# Ethernet.net
KiCad netlist of a schematic drawn in Altium Designer
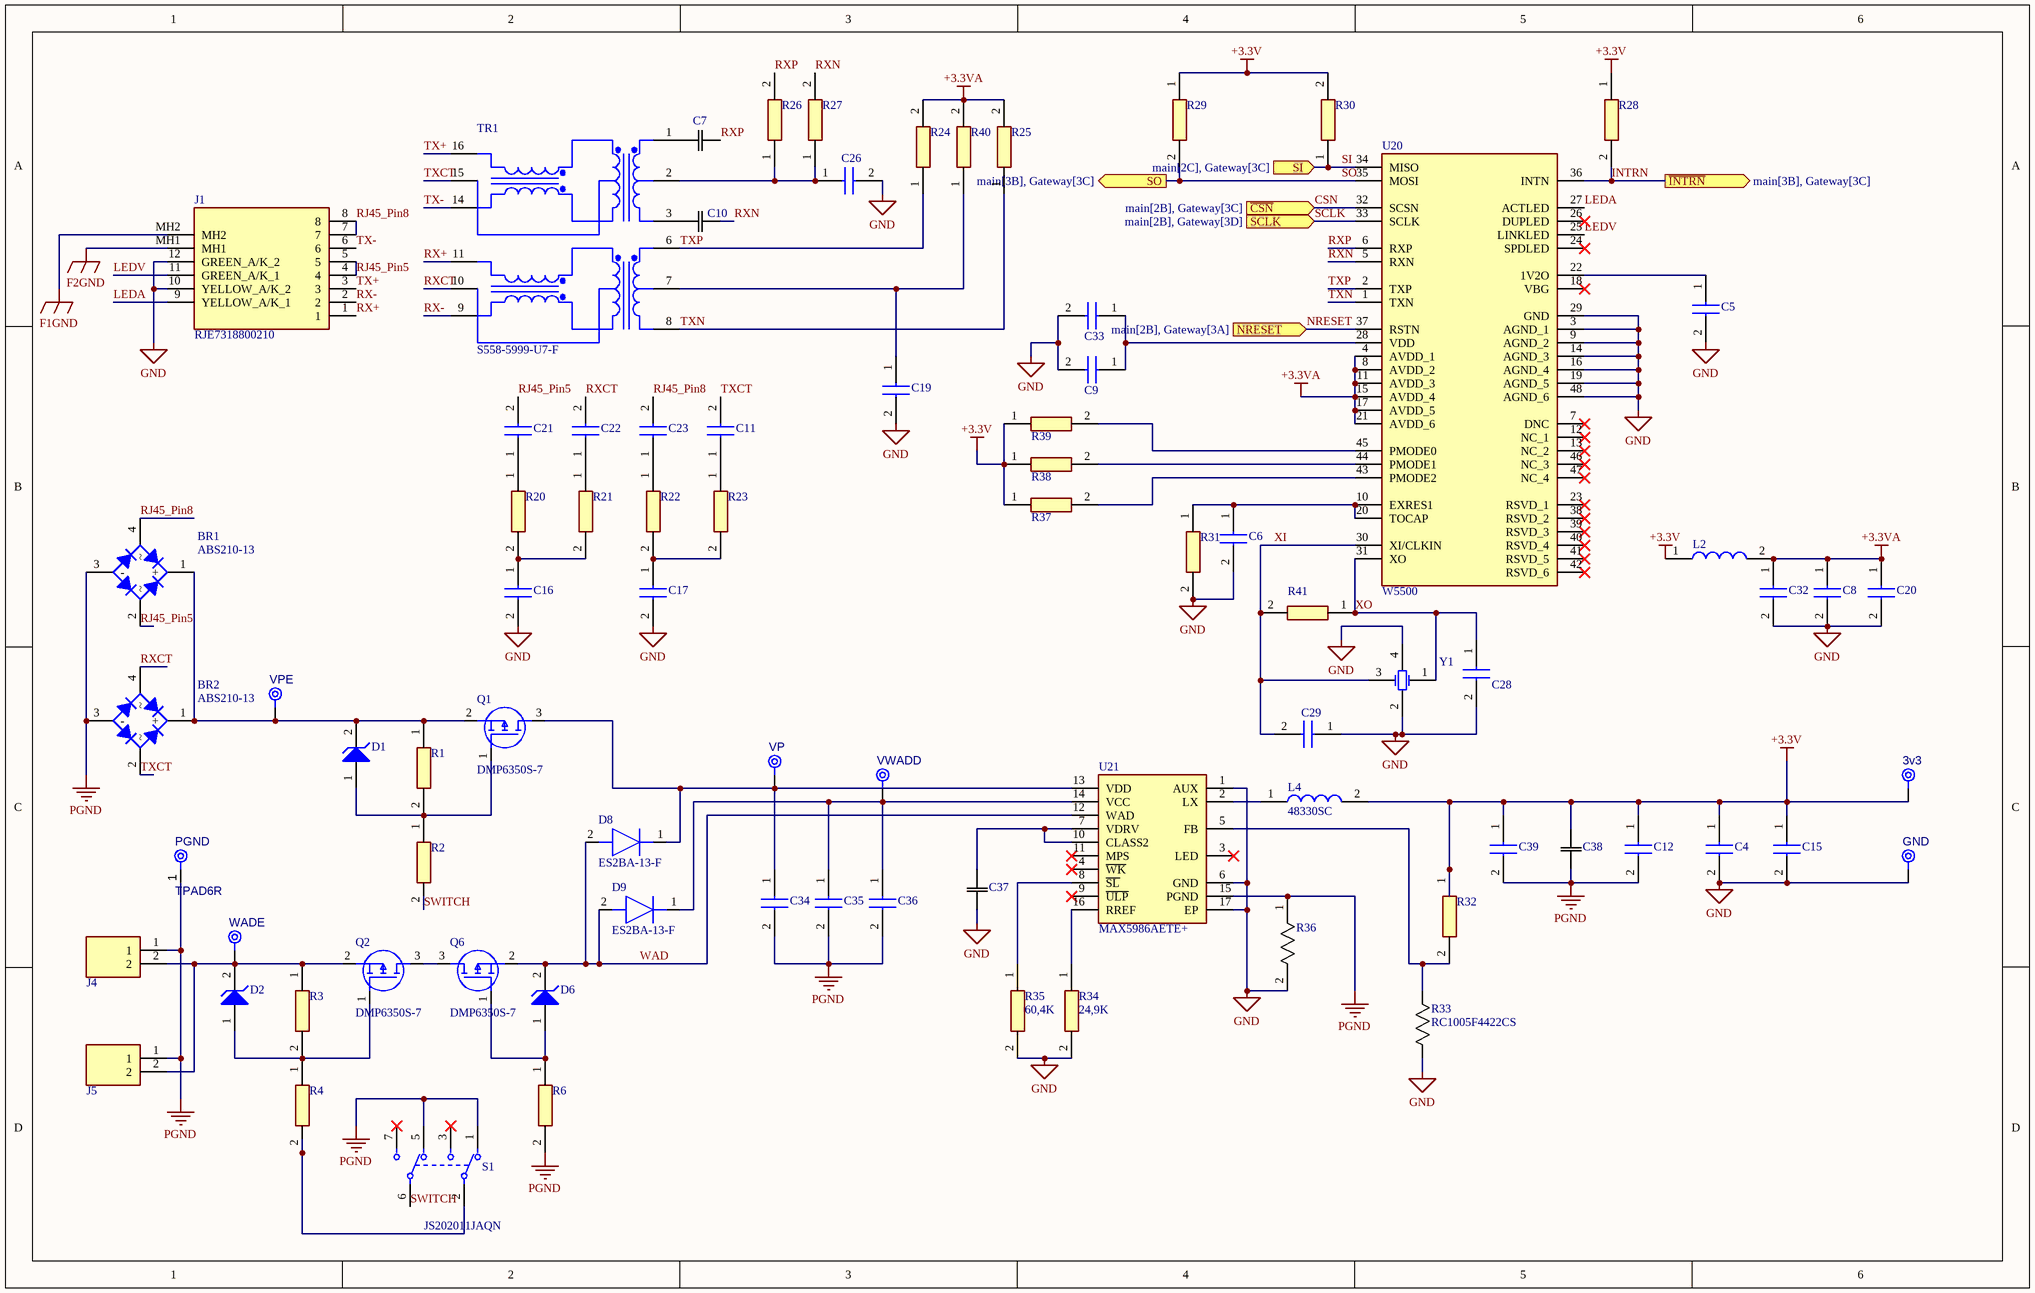
[diagram p0: Ethernet.SchDoc]

(export (version "E")
  (design (tool "Eeschema 10.0.6"))
  (components
    (comp (ref "3v3")
      (value "TPAD6R")
      (footprint "TP06R")
      (description "0.6mm round")
      (libsource (lib "marina santos") (part "CMP-001-0001-4"))
    )
    (comp (ref "BR1")
      (value "ABS210-13")
      (footprint "SamacSys:ABS21013")
      (description "Bridge Rectifier")
      (fields (field (name "MOUSER PART NUMBER") "621-ABS210-13"))
      (libsource (lib "SamacSys") (part "ABS210-13"))
    )
    (comp (ref "BR2")
      (value "ABS210-13")
      (footprint "SamacSys:ABS21013")
      (description "Bridge Rectifier")
      (fields (field (name "MOUSER PART NUMBER") "621-ABS210-13"))
      (libsource (lib "SamacSys") (part "ABS210-13"))
    )
    (comp (ref "C4")
      (value "C1005X7R1C104KT")
      (footprint "SamacSys:CAPC1005X55N")
      (description "Capacitor")
      (libsource (lib "*") (part "C1005X7R1C104KT"))
    )
    (comp (ref "C5")
      (value "CL05B103KO5NNNC")
      (footprint "SamacSys:CAPC1005X55N")
      (description "Capacitor 10n")
      (libsource (lib "*") (part "CL05B103KO5NNNC"))
    )
    (comp (ref "C6")
      (value "JMK105BC6475MV-F")
      (footprint "SamacSys:CAPC1006X65N")
      (description "Capacitor 4,7u")
      (fields (field (name "MOUSER PART NUMBER") "963-JMK105BC6475MV-F"))
      (libsource (lib "*") (part "JMK105BC6475MV-F"))
    )
    (comp (ref "C7")
      (value "CL05X105KP5NNNC")
      (footprint "CAP_CL05_SAM")
      (description "No Description Available")
      (libsource (lib "CL05X105KP5NNNC") (part "CL05X105KP5NNNC"))
    )
    (comp (ref "C8")
      (value "C1005X7R1C104KT")
      (footprint "SamacSys:CAPC1005X55N")
      (description "Capacitor 100n")
      (libsource (lib "*") (part "C1005X7R1C104KT"))
    )
    (comp (ref "C9")
      (value "C1005X7R1C104KT")
      (footprint "SamacSys:CAPC1005X55N")
      (description "Capacitor 100n")
      (libsource (lib "*") (part "C1005X7R1C104KT"))
    )
    (comp (ref "C10")
      (value "CL05X105KP5NNNC")
      (footprint "CAP_CL05_SAM")
      (description "No Description Available")
      (libsource (lib "CL05X105KP5NNNC") (part "CL05X105KP5NNNC"))
    )
    (comp (ref "C11")
      (value "C1608JB2A223M080AA")
      (footprint "SamacSys:C1608_Commercial")
      (description "Capacitor")
      (fields (field (name "MOUSER PART NUMBER") "810-C1608JB2A223M08A"))
      (libsource (lib "*") (part "C1608JB2A223M080AA"))
    )
    (comp (ref "C12")
      (value "C1005X7R1C104KT")
      (footprint "SamacSys:CAPC1005X55N")
      (description "Capacitor")
      (libsource (lib "*") (part "C1005X7R1C104KT"))
    )
    (comp (ref "C15")
      (value "CL05A106MP8NUB8")
      (footprint "SamacSys:CAPC1005X90N")
      (description "Capacitor 10u")
      (fields (field (name "MOUSER PART NUMBER") "187-CL05A106MP8NUB8"))
      (libsource (lib "*") (part "CL05A106MP8NUB8"))
    )
    (comp (ref "C16")
      (value "CL31B102KJHNNNE")
      (footprint "SamacSys:CAPC3216X180N")
      (description "Capacitor")
      (fields (field (name "MOUSER PART NUMBER") "187-CL31B102KJHNNNE"))
      (libsource (lib "*") (part "CL31B102KJHNNNE"))
    )
    (comp (ref "C17")
      (value "CL31B102KJHNNNE")
      (footprint "SamacSys:CAPC3216X180N")
      (description "Capacitor")
      (fields (field (name "MOUSER PART NUMBER") "187-CL31B102KJHNNNE"))
      (libsource (lib "*") (part "CL31B102KJHNNNE"))
    )
    (comp (ref "C19")
      (value "GRM155R71H223KA12D")
      (footprint "SamacSys:GRM15x")
      (description "Capacitor")
      (fields (field (name "MOUSER PART NUMBER") "81-GRM155R71H223KA12"))
      (libsource (lib "*") (part "GRM155R71H223KA12D"))
    )
    (comp (ref "C20")
      (value "CL05B103KO5NNNC")
      (footprint "SamacSys:CAPC1005X55N")
      (description "Capacitor 10n")
      (libsource (lib "*") (part "CL05B103KO5NNNC"))
    )
    (comp (ref "C21")
      (value "C1608JB2A223M080AA")
      (footprint "SamacSys:C1608_Commercial")
      (description "Capacitor")
      (fields (field (name "MOUSER PART NUMBER") "810-C1608JB2A223M08A"))
      (libsource (lib "*") (part "C1608JB2A223M080AA"))
    )
    (comp (ref "C22")
      (value "C1608JB2A223M080AA")
      (footprint "SamacSys:C1608_Commercial")
      (description "Capacitor")
      (fields (field (name "MOUSER PART NUMBER") "810-C1608JB2A223M08A"))
      (libsource (lib "*") (part "C1608JB2A223M080AA"))
    )
    (comp (ref "C23")
      (value "C1608JB2A223M080AA")
      (footprint "SamacSys:C1608_Commercial")
      (description "Capacitor")
      (fields (field (name "MOUSER PART NUMBER") "810-C1608JB2A223M08A"))
      (libsource (lib "*") (part "C1608JB2A223M080AA"))
    )
    (comp (ref "C26")
      (value "C1005X5R1E104K050BC")
      (footprint "SamacSys:CAPC1005X55N")
      (description "Capacitor")
      (fields (field (name "MOUSER PART NUMBER") "810-C1005X5R1E104K"))
      (libsource (lib "*") (part "C1005X5R1E104K050BC"))
    )
    (comp (ref "C28")
      (value "C1005C0G1H150JT")
      (footprint "SamacSys:CAPC1005X55N")
      (description "Capacitor 15pF")
      (fields (field (name "MANUFACTURER_PART_NUMBER") "CC0402JRNPO9BN150"))
      (libsource (lib "*") (part "CC0402JRNPO9BN150"))
    )
    (comp (ref "C29")
      (value "C1005C0G1H150JT")
      (footprint "SamacSys:CAPC1005X55N")
      (description "Capacitor 15pF")
      (fields (field (name "MANUFACTURER_PART_NUMBER") "CC0402JRNPO9BN150"))
      (libsource (lib "*") (part "CC0402JRNPO9BN150"))
    )
    (comp (ref "C32")
      (value "JMK105BC6475MV-F")
      (footprint "SamacSys:CAPC1006X65N")
      (description "Capacitor 4,7u")
      (fields (field (name "MOUSER PART NUMBER") "963-JMK105BC6475MV-F"))
      (libsource (lib "*") (part "JMK105BC6475MV-F"))
    )
    (comp (ref "C33")
      (value "JMK105BC6475MV-F")
      (footprint "SamacSys:CAPC1006X65N")
      (description "Capacitor 4,7u")
      (fields (field (name "MOUSER PART NUMBER") "963-JMK105BC6475MV-F"))
      (libsource (lib "*") (part "JMK105BC6475MV-F"))
    )
    (comp (ref "C34")
      (value "CC0805KKX7R0BB683")
      (footprint "SamacSys:CAPC2012X145N")
      (description "Capacitor 0,068u")
      (fields (field (name "MOUSER PART NUMBER") "603-CC0805KR0BB683"))
      (libsource (lib "*") (part "CC0805KKX7R0BB683"))
    )
    (comp (ref "C35")
      (value "CL21Y105KCYVPNE")
      (footprint "SamacSys:CAPC2012X145N")
      (description "Capacitor")
      (libsource (lib "SamacSys") (part "CL21Y105KCYVPNE"))
    )
    (comp (ref "C36")
      (value "GRM32ER71J106KA12L")
      (footprint "SamacSys:CAPC3225X270N")
      (description "Capacitor 10u")
      (fields (field (name "MOUSER PART NUMBER") "81-GRM32ER71J106KA2L"))
      (libsource (lib "*") (part "GRM32ER71J106KA12L"))
    )
    (comp (ref "C37")
      (value "CL05X105KP5NNNC")
      (footprint "CAP_CL_05_SAM")
      (description "1u")
      (libsource (lib "CL05X105KP5NNNC") (part "CL05X105KP5NNNC"))
    )
    (comp (ref "C38")
      (value "CL05X105KP5NNNC")
      (footprint "CAP_CL_05_SAM")
      (description "No Description Available")
      (libsource (lib "CL05X105KP5NNNC") (part "CL05X105KP5NNNC"))
    )
    (comp (ref "C39")
      (value "GRM21BR61A476ME15L")
      (footprint "SamacSys:CAPC2012X145N")
      (description "Capacitor")
      (fields (field (name "MOUSER PART NUMBER") "81-GRM21BR61A476ME5L"))
      (libsource (lib "*") (part "GRM21BR61A476ME15L"))
    )
    (comp (ref "D1")
      (value "MMSZ5240B-7-F")
      (footprint "SamacSys:SOD3716X145N")
      (description "D2")
      (fields (field (name "MOUSER PART NUMBER") "621-MMSZ5240B-F"))
      (libsource (lib "SamacSys") (part "MMSZ5240B-7-F"))
    )
    (comp (ref "D2")
      (value "MMSZ5240B-7-F")
      (footprint "SamacSys:SOD3716X145N")
      (description "D2")
      (fields (field (name "MOUSER PART NUMBER") "621-MMSZ5240B-F"))
      (libsource (lib "SamacSys") (part "MMSZ5240B-7-F"))
    )
    (comp (ref "D6")
      (value "MMSZ5240B-7-F")
      (footprint "SamacSys:SOD3716X145N")
      (description "D2")
      (fields (field (name "MOUSER PART NUMBER") "621-MMSZ5240B-F"))
      (libsource (lib "SamacSys") (part "MMSZ5240B-7-F"))
    )
    (comp (ref "D8")
      (value "ES2BA-13-F")
      (footprint "SamacSys:DIOM5226X230N")
      (description "Diode")
      (fields (field (name "MOUSER PART NUMBER") "621-ES2BA-F"))
      (libsource (lib "*") (part "ES2BA-13-F"))
    )
    (comp (ref "D9")
      (value "ES2BA-13-F")
      (footprint "SamacSys:DIOM5226X230N")
      (description "Diode")
      (fields (field (name "MOUSER PART NUMBER") "621-ES2BA-F"))
      (libsource (lib "*") (part "ES2BA-13-F"))
    )
    (comp (ref "GND")
      (value "TPAD6R")
      (footprint "TP06R")
      (description "0.6mm round")
      (libsource (lib "marina santos") (part "CMP-001-0001-4"))
    )
    (comp (ref "J1")
      (value "RJE7318800210")
      (footprint "SamacSys:RJE7318800210")
      (description "Connector")
      (fields (field (name "MOUSER PART NUMBER") "523-RJE7318800210"))
      (libsource (lib "SamacSys") (part "RJE7318800210"))
    )
    (comp (ref "J4")
      (value "OQ0232510000G")
      (footprint "SamacSys:OQ0232510000G")
      (description "Connector")
      (fields (field (name "MOUSER PART NUMBER") "649-220110-D021A01LF"))
      (libsource (lib "*") (part "OQ0232510000G"))
    )
    (comp (ref "J5")
      (value "OQ0232510000G")
      (footprint "SamacSys:OQ0232510000G")
      (description "Connector")
      (fields (field (name "MOUSER PART NUMBER") "649-220110-D021A01LF"))
      (libsource (lib "*") (part "OQ0232510000G"))
    )
    (comp (ref "L2")
      (value "FBMH1608HM101-T")
      (footprint "SamacSys:INDC1608X90N")
      (description "Ferrite Bead")
      (fields (field (name "MOUSER PART NUMBER") "963-FBMH1608HM101-T"))
      (libsource (lib "SamacSys") (part "FBMH1608HM101-T"))
    )
    (comp (ref "L4")
      (value "48330SC")
      (footprint "SamacSys:48101SC")
      (description "Inductor")
      (fields
        (field (name "MANUFACTURER_PART_NUMBER") "48101SC")
        (field (name "MOUSER PART NUMBER") "580-48101SC")
      )
      (libsource (lib "SamacSys") (part "48101SC"))
    )
    (comp (ref "PGND")
      (value "TPAD6R")
      (footprint "TP06R")
      (description "0.6mm round")
      (libsource (lib "") (part "CMP-001-0001-4_1"))
    )
    (comp (ref "Q1")
      (value "DMP6350S-7")
      (footprint "SamacSys:SOT96P240X110-3N")
      (description "MOSFET (P-Channel)")
      (fields (field (name "MOUSER PART NUMBER") "621-DMP6350S-7"))
      (libsource (lib "*") (part "DMP6350S-7"))
    )
    (comp (ref "Q2")
      (value "DMP6350S-7")
      (footprint "SamacSys:SOT96P240X110-3N")
      (description "MOSFET (P-Channel)")
      (fields (field (name "MOUSER PART NUMBER") "621-DMP6350S-7"))
      (libsource (lib "*") (part "DMP6350S-7"))
    )
    (comp (ref "Q6")
      (value "DMP6350S-7")
      (footprint "SamacSys:SOT96P240X110-3N")
      (description "MOSFET (P-Channel)")
      (fields (field (name "MOUSER PART NUMBER") "621-DMP6350S-7"))
      (libsource (lib "*") (part "DMP6350S-7"))
    )
    (comp (ref "R1")
      (value "R0402_1%_100_K__RC0402FR-07100KL_")
      (footprint "SamacSys:RESC1005X40N")
      (description "Resistor 100k")
      (fields (field (name "MANUFACTURER_PART_NUMBER") "R0402 1% 100 K (RC0402FR-07100KL)"))
      (libsource (lib "*") (part "R0402_1%_100_K__RC0402FR-07100KL_"))
    )
    (comp (ref "R2")
      (value "R0402_1%_100_K__RC0402FR-07100KL_")
      (footprint "SamacSys:RESC1005X40N")
      (description "Resistor 100k")
      (fields (field (name "MANUFACTURER_PART_NUMBER") "R0402 1% 100 K (RC0402FR-07100KL)"))
      (libsource (lib "*") (part "R0402_1%_100_K__RC0402FR-07100KL_"))
    )
    (comp (ref "R3")
      (value "R0402_1%_100_K__RC0402FR-07100KL_")
      (footprint "SamacSys:RESC1005X40N")
      (description "Resistor 100k")
      (fields (field (name "MANUFACTURER_PART_NUMBER") "R0402 1% 100 K (RC0402FR-07100KL)"))
      (libsource (lib "*") (part "R0402_1%_100_K__RC0402FR-07100KL_"))
    )
    (comp (ref "R4")
      (value "R0402_1%_100_K__RC0402FR-07100KL_")
      (footprint "SamacSys:RESC1005X40N")
      (description "Resistor 100k")
      (fields (field (name "MANUFACTURER_PART_NUMBER") "R0402 1% 100 K (RC0402FR-07100KL)"))
      (libsource (lib "*") (part "R0402_1%_100_K__RC0402FR-07100KL_"))
    )
    (comp (ref "R6")
      (value "R0402_1%_100_K__RC0402FR-07100KL_")
      (footprint "SamacSys:RESC1005X40N")
      (description "Resistor 100k")
      (fields (field (name "MANUFACTURER_PART_NUMBER") "R0402 1% 100 K (RC0402FR-07100KL)"))
      (libsource (lib "*") (part "R0402_1%_100_K__RC0402FR-07100KL_"))
    )
    (comp (ref "R20")
      (value "RC0603FR-0775RL")
      (footprint "SamacSys:RESC1608X55N")
      (description "Resistor")
      (fields (field (name "MOUSER PART NUMBER") "603-RC0603FR-0775RL"))
      (libsource (lib "*") (part "RC0603FR-0775RL"))
    )
    (comp (ref "R21")
      (value "RC0603FR-0775RL")
      (footprint "SamacSys:RESC1608X55N")
      (description "Resistor")
      (fields (field (name "MOUSER PART NUMBER") "603-RC0603FR-0775RL"))
      (libsource (lib "*") (part "RC0603FR-0775RL"))
    )
    (comp (ref "R22")
      (value "RC0603FR-0775RL")
      (footprint "SamacSys:RESC1608X55N")
      (description "Resistor")
      (fields (field (name "MOUSER PART NUMBER") "603-RC0603FR-0775RL"))
      (libsource (lib "*") (part "RC0603FR-0775RL"))
    )
    (comp (ref "R23")
      (value "RC0603FR-0775RL")
      (footprint "SamacSys:RESC1608X55N")
      (description "Resistor")
      (fields (field (name "MOUSER PART NUMBER") "603-RC0603FR-0775RL"))
      (libsource (lib "*") (part "RC0603FR-0775RL"))
    )
    (comp (ref "R24")
      (value "RC0402FR-0749R9L")
      (footprint "SamacSys:RESC1005X40N")
      (description "Resistor 49,9 ohms")
      (fields (field (name "MOUSER PART NUMBER") "603-RC0402FR-0749R9L"))
      (libsource (lib "*") (part "RC0402FR-0749R9L"))
    )
    (comp (ref "R25")
      (value "RC0402FR-0749R9L")
      (footprint "SamacSys:RESC1005X40N")
      (description "Resistor 49,9 ohms")
      (fields (field (name "MOUSER PART NUMBER") "603-RC0402FR-0749R9L"))
      (libsource (lib "*") (part "RC0402FR-0749R9L"))
    )
    (comp (ref "R26")
      (value "RC0402FR-0782RL")
      (footprint "SamacSys:RESC1005X40N")
      (description "Resistor")
      (fields (field (name "MOUSER PART NUMBER") "603-RC0402FR-0782RL"))
      (libsource (lib "*") (part "RC0402FR-0782RL"))
    )
    (comp (ref "R27")
      (value "RC0402FR-0782RL")
      (footprint "SamacSys:RESC1005X40N")
      (description "Resistor")
      (fields (field (name "MOUSER PART NUMBER") "603-RC0402FR-0782RL"))
      (libsource (lib "*") (part "RC0402FR-0782RL"))
    )
    (comp (ref "R28")
      (value "RC0402FR-074K7L")
      (footprint "SamacSys:RESC1005X40N")
      (description "Resistor 4,7K")
      (fields (field (name "MOUSER PART NUMBER") "603-RC0402FR-074K7L"))
      (libsource (lib "*") (part "RC0402FR-074K7L"))
    )
    (comp (ref "R29")
      (value "RC0402FR-074K7L")
      (footprint "SamacSys:RESC1005X40N")
      (description "Resistor 4,7K")
      (fields (field (name "MOUSER PART NUMBER") "603-RC0402FR-074K7L"))
      (libsource (lib "*") (part "RC0402FR-074K7L"))
    )
    (comp (ref "R30")
      (value "RC0402FR-074K7L")
      (footprint "SamacSys:RESC1005X40N")
      (description "Resistor 4,7 K")
      (fields (field (name "MOUSER PART NUMBER") "603-RC0402FR-074K7L"))
      (libsource (lib "") (part "RC0402FR-074K7L_1"))
    )
    (comp (ref "R31")
      (value "RC0402FR-0712K4L")
      (footprint "SamacSys:RESC1005X40N")
      (description "Resistor 12,4K")
      (fields (field (name "MOUSER PART NUMBER") "603-RC0402FR-0712K4L"))
      (libsource (lib "*") (part "RC0402FR-0712K4L"))
    )
    (comp (ref "R32")
      (value "RC0402FR-0775KL")
      (footprint "SamacSys:RESC1005X40N")
      (description "Resistor")
      (fields (field (name "MOUSER PART NUMBER") "603-RC0402FR-0775KL"))
      (libsource (lib "*") (part "RC0402FR-0775KL"))
    )
    (comp (ref "R33")
      (value "RC1005F4422CS")
      (footprint "RES_1005_SAM-M")
      (description "No Description Available")
      (libsource (lib "RC1005F4422CS") (part "RC1005F4422CS"))
    )
    (comp (ref "R34")
      (value "24,9K")
      (footprint "SamacSys:RESC1005X40N")
      (description "Resistor")
      (fields
        (field (name "MANUFACTURER_PART_NUMBER") "RC0402FR-0724K9L")
        (field (name "MOUSER PART NUMBER") "603-RC0402FR-0724K9L")
      )
      (libsource (lib "*") (part "RC0402FR-0724K9L"))
    )
    (comp (ref "R35")
      (value "60,4K")
      (footprint "SamacSys:RESC1005X40N")
      (description "Resistor 60,4K")
      (fields
        (field (name "MANUFACTURER_PART_NUMBER") "RC0402FR-0760K4L")
        (field (name "MOUSER PART NUMBER") "603-RC0402FR-0760K4L")
      )
      (libsource (lib "*") (part "RC0402FR-0760K4L"))
    )
    (comp (ref "R36")
      (value "RC0805JR-070RL")
      (footprint "SamacSys:CAPC2012X60N")
      (description "Capacitor 0 ohms")
      (fields (field (name "MOUSER PART NUMBER") "603-RC0805JR-070RL"))
      (libsource (lib "SamacSys") (part "RC0805JR-070RL"))
    )
    (comp (ref "R37")
      (value "RC0402FR-0710KL")
      (footprint "SamacSys:RESC1005X40N")
      (description "Resistor 10K")
      (fields (field (name "MOUSER PART NUMBER") "603-RC0402FR-0710KL"))
      (libsource (lib "*") (part "RC0402FR-0710KL"))
    )
    (comp (ref "R38")
      (value "RC0402FR-0710KL")
      (footprint "SamacSys:RESC1005X40N")
      (description "Resistor 10K")
      (fields (field (name "MOUSER PART NUMBER") "603-RC0402FR-0710KL"))
      (libsource (lib "*") (part "RC0402FR-0710KL"))
    )
    (comp (ref "R39")
      (value "RC0402FR-0710KL")
      (footprint "SamacSys:RESC1005X40N")
      (description "Resistor 10K")
      (fields (field (name "MOUSER PART NUMBER") "603-RC0402FR-0710KL"))
      (libsource (lib "*") (part "RC0402FR-0710KL"))
    )
    (comp (ref "R40")
      (value "RC0402FR-0710RL")
      (footprint "SamacSys:RESC1005X40N")
      (description "Resistor 10 ohms")
      (fields (field (name "MOUSER PART NUMBER") "603-RC0402FR-0710RL"))
      (libsource (lib "*") (part "RC0402FR-0710RL"))
    )
    (comp (ref "R41")
      (value "RC0402FR-071ML")
      (footprint "SamacSys:RESC1005X40N")
      (description "Resistor 1M")
      (fields (field (name "MOUSER PART NUMBER") "603-RC0402FR-071ML"))
      (libsource (lib "*") (part "RC0402FR-071ML"))
    )
    (comp (ref "S1")
      (value "JS202011JAQN")
      (footprint "C&K_0_MFG")
      (libsource (lib "Switch_C&K_JS202011JAQN_eec") (part "JS202011JAQN"))
    )
    (comp (ref "TR1")
      (value "S558-5999-U7-F")
      (footprint "SamacSys:SOIC127P920X571-16N")
      (description "Integrated Circuit")
      (fields (field (name "MOUSER PART NUMBER") "530-S558-5999-U7-F"))
      (libsource (lib "SamacSys") (part "S558-5999-U7-F"))
    )
    (comp (ref "U20")
      (value "W5500")
      (footprint "SamacSys:QFP50P900X900X160-48N")
      (description "Integrated Circuit")
      (fields (field (name "MOUSER PART NUMBER") "950-W5500"))
      (libsource (lib "SamacSys") (part "W5500"))
    )
    (comp (ref "U21")
      (value "MAX5986AETE+")
      (footprint "SamacSys:QFN80P500X500X80-17N")
      (description "Integrated Circuit")
      (fields (field (name "MOUSER PART NUMBER") "700-MAX5986AETE+"))
      (libsource (lib "SamacSys") (part "MAX5986AETE+"))
    )
    (comp (ref "VP")
      (value "TPAD6R")
      (footprint "TP06R")
      (description "0.6mm round")
      (libsource (lib "marina santos") (part "CMP-001-0001-4"))
    )
    (comp (ref "VPE")
      (value "TPAD6R")
      (footprint "TP06R")
      (description "0.6mm round")
      (libsource (lib "marina santos") (part "CMP-001-0001-4"))
    )
    (comp (ref "VWADD")
      (value "TPAD6R")
      (footprint "TP06R")
      (description "0.6mm round")
      (libsource (lib "marina santos") (part "CMP-001-0001-4"))
    )
    (comp (ref "WADE")
      (value "TPAD6R")
      (footprint "TP06R")
      (description "0.6mm round")
      (libsource (lib "marina santos") (part "CMP-001-0001-4"))
    )
    (comp (ref "Y1")
      (value "RH100-25.000-12-F-1010-TR")
      (footprint "SamacSys:RH1002500012F1010TR")
      (description "Crystal or Oscillator")
      (libsource (lib "SamacSys") (part "RH100-25.000-12-F-1010-TR"))
    )
  )
  (nets
    (net (code "1") (name "+3.3V") (class "Default")
      (node (ref "3v3") (pin "1") (pinfunction "TP_1") (pintype "passive"))
      (node (ref "C12") (pin "1") (pinfunction "1_1") (pintype "passive"))
      (node (ref "C15") (pin "1") (pinfunction "1_1") (pintype "passive"))
      (node (ref "C38") (pin "2") (pinfunction "2_2") (pintype "passive"))
      (node (ref "C39") (pin "1") (pinfunction "1_1") (pintype "passive"))
      (node (ref "C4") (pin "1") (pinfunction "1_1") (pintype "passive"))
      (node (ref "L2") (pin "1") (pinfunction "1_1") (pintype "passive"))
      (node (ref "L4") (pin "2") (pinfunction "2_2") (pintype "passive"))
      (node (ref "R28") (pin "1") (pinfunction "1_1") (pintype "passive"))
      (node (ref "R29") (pin "1") (pinfunction "1_1") (pintype "passive"))
      (node (ref "R30") (pin "2") (pinfunction "2_2") (pintype "passive"))
      (node (ref "R32") (pin "1") (pinfunction "1_1") (pintype "passive"))
      (node (ref "R37") (pin "1") (pinfunction "1_1") (pintype "passive"))
      (node (ref "R38") (pin "1") (pinfunction "1_1") (pintype "passive"))
      (node (ref "R39") (pin "1") (pinfunction "1_1") (pintype "passive"))
    )
    (net (code "2") (name "+3.3VA") (class "Default")
      (node (ref "C20") (pin "1") (pinfunction "1_1") (pintype "passive"))
      (node (ref "C32") (pin "1") (pinfunction "1_1") (pintype "passive"))
      (node (ref "C8") (pin "1") (pinfunction "1_1") (pintype "passive"))
      (node (ref "L2") (pin "2") (pinfunction "2_2") (pintype "passive"))
      (node (ref "R24") (pin "2") (pinfunction "2_2") (pintype "passive"))
      (node (ref "R25") (pin "2") (pinfunction "2_2") (pintype "passive"))
      (node (ref "R40") (pin "2") (pinfunction "2_2") (pintype "passive"))
      (node (ref "U20") (pin "11") (pinfunction "AVDD_3_11") (pintype "passive"))
      (node (ref "U20") (pin "15") (pinfunction "AVDD_4_15") (pintype "passive"))
      (node (ref "U20") (pin "17") (pinfunction "AVDD_5_17") (pintype "passive"))
      (node (ref "U20") (pin "21") (pinfunction "AVDD_6_21") (pintype "passive"))
      (node (ref "U20") (pin "4") (pinfunction "AVDD_1_4") (pintype "passive"))
      (node (ref "U20") (pin "8") (pinfunction "AVDD_2_8") (pintype "passive"))
    )
    (net (code "3") (name "/CSN") (class "Default")
      (node (ref "U20") (pin "32") (pinfunction "SCSN_32") (pintype "passive"))
    )
    (net (code "4") (name "/INTRN") (class "Default")
      (node (ref "R28") (pin "2") (pinfunction "2_2") (pintype "passive"))
      (node (ref "U20") (pin "36") (pinfunction "INTN_36") (pintype "passive"))
    )
    (net (code "5") (name "/LEDA") (class "Default")
      (node (ref "J1") (pin "9") (pinfunction "YELLOW_A/K_1_9") (pintype "passive"))
      (node (ref "U20") (pin "27") (pinfunction "ACTLED_27") (pintype "passive"))
    )
    (net (code "6") (name "/LEDV") (class "Default")
      (node (ref "J1") (pin "11") (pinfunction "GREEN_A/K_1_11") (pintype "passive"))
      (node (ref "U20") (pin "25") (pinfunction "LINKLED_25") (pintype "passive"))
    )
    (net (code "7") (name "/NRESET") (class "Default")
      (node (ref "U20") (pin "37") (pinfunction "RSTN_37") (pintype "passive"))
    )
    (net (code "8") (name "/RJ45_Pin5") (class "Default")
      (node (ref "BR1") (pin "2") (pinfunction "~_2") (pintype "passive"))
      (node (ref "C21") (pin "2") (pinfunction "2_2") (pintype "passive"))
      (node (ref "J1") (pin "4") (pinfunction "4_4") (pintype "passive"))
      (node (ref "J1") (pin "5") (pinfunction "5_5") (pintype "passive"))
    )
    (net (code "9") (name "/RJ45_Pin8") (class "Default")
      (node (ref "BR1") (pin "4") (pinfunction "~_4") (pintype "passive"))
      (node (ref "C23") (pin "2") (pinfunction "2_2") (pintype "passive"))
      (node (ref "J1") (pin "7") (pinfunction "7_7") (pintype "passive"))
      (node (ref "J1") (pin "8") (pinfunction "8_8") (pintype "passive"))
    )
    (net (code "10") (name "/RX+") (class "Default")
      (node (ref "J1") (pin "1") (pinfunction "1_1") (pintype "passive"))
      (node (ref "TR1") (pin "11") (pinfunction "RX+_11") (pintype "passive"))
    )
    (net (code "11") (name "/RX-") (class "Default")
      (node (ref "J1") (pin "2") (pinfunction "2_2") (pintype "passive"))
      (node (ref "TR1") (pin "9") (pinfunction "RX-_9") (pintype "passive"))
    )
    (net (code "12") (name "/RXCT") (class "Default")
      (node (ref "BR2") (pin "4") (pinfunction "~_4") (pintype "passive"))
      (node (ref "C22") (pin "2") (pinfunction "2_2") (pintype "passive"))
      (node (ref "TR1") (pin "10") (pinfunction "RXCT_10") (pintype "passive"))
    )
    (net (code "13") (name "/RXN") (class "Default")
      (node (ref "C10") (pin "2") (pinfunction "2_2") (pintype "passive"))
      (node (ref "R27") (pin "2") (pinfunction "2_2") (pintype "passive"))
      (node (ref "U20") (pin "5") (pinfunction "RXN_5") (pintype "passive"))
    )
    (net (code "14") (name "/RXP") (class "Default")
      (node (ref "C7") (pin "2") (pinfunction "2_2") (pintype "passive"))
      (node (ref "R26") (pin "2") (pinfunction "2_2") (pintype "passive"))
      (node (ref "U20") (pin "6") (pinfunction "RXP_6") (pintype "passive"))
    )
    (net (code "15") (name "/SCLK") (class "Default")
      (node (ref "U20") (pin "33") (pinfunction "SCLK_33") (pintype "passive"))
    )
    (net (code "16") (name "/SI") (class "Default")
      (node (ref "R30") (pin "1") (pinfunction "1_1") (pintype "passive"))
      (node (ref "U20") (pin "34") (pinfunction "MISO_34") (pintype "passive"))
    )
    (net (code "17") (name "/SO") (class "Default")
      (node (ref "R29") (pin "2") (pinfunction "2_2") (pintype "passive"))
      (node (ref "U20") (pin "35") (pinfunction "MOSI_35") (pintype "passive"))
    )
    (net (code "18") (name "/SWITCH") (class "Default")
      (node (ref "R2") (pin "2") (pinfunction "2_2") (pintype "passive"))
      (node (ref "S1") (pin "6") (pinfunction "2_C_6") (pintype "passive"))
    )
    (net (code "19") (name "/TX+") (class "Default")
      (node (ref "J1") (pin "3") (pinfunction "3_3") (pintype "passive"))
      (node (ref "TR1") (pin "16") (pinfunction "TX+_16") (pintype "passive"))
    )
    (net (code "20") (name "/TX-") (class "Default")
      (node (ref "J1") (pin "6") (pinfunction "6_6") (pintype "passive"))
      (node (ref "TR1") (pin "14") (pinfunction "TX-_14") (pintype "passive"))
    )
    (net (code "21") (name "/TXCT") (class "Default")
      (node (ref "BR2") (pin "2") (pinfunction "~_2") (pintype "passive"))
      (node (ref "C11") (pin "2") (pinfunction "2_2") (pintype "passive"))
      (node (ref "TR1") (pin "15") (pinfunction "TXCT_15") (pintype "passive"))
    )
    (net (code "22") (name "/TXN") (class "Default")
      (node (ref "R25") (pin "1") (pinfunction "1_1") (pintype "passive"))
      (node (ref "TR1") (pin "8") (pinfunction "RD-_8") (pintype "passive"))
      (node (ref "U20") (pin "1") (pinfunction "TXN_1") (pintype "passive"))
    )
    (net (code "23") (name "/TXP") (class "Default")
      (node (ref "R24") (pin "1") (pinfunction "1_1") (pintype "passive"))
      (node (ref "TR1") (pin "6") (pinfunction "RD+_6") (pintype "passive"))
      (node (ref "U20") (pin "2") (pinfunction "TXP_2") (pintype "passive"))
    )
    (net (code "24") (name "/WAD") (class "Default")
      (node (ref "D6") (pin "2") (pinfunction "A_2") (pintype "passive"))
      (node (ref "D8") (pin "2") (pinfunction "A_2") (pintype "passive"))
      (node (ref "D9") (pin "2") (pinfunction "A_2") (pintype "passive"))
      (node (ref "Q6") (pin "2") (pinfunction "S_2") (pintype "passive"))
      (node (ref "U21") (pin "12") (pinfunction "WAD_12") (pintype "passive"))
    )
    (net (code "25") (name "/XI") (class "Default")
      (node (ref "C29") (pin "2") (pinfunction "2_2") (pintype "passive"))
      (node (ref "R41") (pin "2") (pinfunction "2_2") (pintype "passive"))
      (node (ref "U20") (pin "30") (pinfunction "XI/CLKIN_30") (pintype "passive"))
      (node (ref "Y1") (pin "3") (pinfunction "CRYSTAL_2_3") (pintype "passive"))
    )
    (net (code "26") (name "/XO") (class "Default")
      (node (ref "C28") (pin "1") (pinfunction "1_1") (pintype "passive"))
      (node (ref "R41") (pin "1") (pinfunction "1_1") (pintype "passive"))
      (node (ref "U20") (pin "31") (pinfunction "XO_31") (pintype "passive"))
      (node (ref "Y1") (pin "1") (pinfunction "CRYSTAL_1_1") (pintype "passive"))
    )
    (net (code "27") (name "F1GND") (class "Default")
      (node (ref "J1") (pin "MH2") (pinfunction "MH2_MH2") (pintype "passive"))
    )
    (net (code "28") (name "F2GND") (class "Default")
      (node (ref "J1") (pin "MH1") (pinfunction "MH1_MH1") (pintype "passive"))
    )
    (net (code "29") (name "GND") (class "Default")
      (node (ref "C15") (pin "2") (pinfunction "2_2") (pintype "passive"))
      (node (ref "C16") (pin "2") (pinfunction "2_2") (pintype "passive"))
      (node (ref "C17") (pin "2") (pinfunction "2_2") (pintype "passive"))
      (node (ref "C19") (pin "2") (pinfunction "2_2") (pintype "passive"))
      (node (ref "C20") (pin "2") (pinfunction "2_2") (pintype "passive"))
      (node (ref "C26") (pin "2") (pinfunction "2_2") (pintype "passive"))
      (node (ref "C28") (pin "2") (pinfunction "2_2") (pintype "passive"))
      (node (ref "C29") (pin "1") (pinfunction "1_1") (pintype "passive"))
      (node (ref "C32") (pin "2") (pinfunction "2_2") (pintype "passive"))
      (node (ref "C33") (pin "2") (pinfunction "2_2") (pintype "passive"))
      (node (ref "C37") (pin "1") (pinfunction "1_1") (pintype "passive"))
      (node (ref "C4") (pin "2") (pinfunction "2_2") (pintype "passive"))
      (node (ref "C5") (pin "2") (pinfunction "2_2") (pintype "passive"))
      (node (ref "C6") (pin "2") (pinfunction "2_2") (pintype "passive"))
      (node (ref "C8") (pin "2") (pinfunction "2_2") (pintype "passive"))
      (node (ref "C9") (pin "2") (pinfunction "2_2") (pintype "passive"))
      (node (ref "GND") (pin "1") (pinfunction "TP_1") (pintype "passive"))
      (node (ref "J1") (pin "10") (pinfunction "YELLOW_A/K_2_10") (pintype "passive"))
      (node (ref "J1") (pin "12") (pinfunction "GREEN_A/K_2_12") (pintype "passive"))
      (node (ref "R31") (pin "2") (pinfunction "2_2") (pintype "passive"))
      (node (ref "R33") (pin "1") (pinfunction "1_1") (pintype "passive"))
      (node (ref "R34") (pin "2") (pinfunction "2_2") (pintype "passive"))
      (node (ref "R35") (pin "2") (pinfunction "2_2") (pintype "passive"))
      (node (ref "R36") (pin "2") (pinfunction "2_2") (pintype "passive"))
      (node (ref "U20") (pin "14") (pinfunction "AGND_3_14") (pintype "passive"))
      (node (ref "U20") (pin "16") (pinfunction "AGND_4_16") (pintype "passive"))
      (node (ref "U20") (pin "19") (pinfunction "AGND_5_19") (pintype "passive"))
      (node (ref "U20") (pin "29") (pinfunction "GND_29") (pintype "passive"))
      (node (ref "U20") (pin "3") (pinfunction "AGND_1_3") (pintype "passive"))
      (node (ref "U20") (pin "48") (pinfunction "AGND_6_48") (pintype "passive"))
      (node (ref "U20") (pin "9") (pinfunction "AGND_2_9") (pintype "passive"))
      (node (ref "U21") (pin "1") (pinfunction "AUX_1") (pintype "passive"))
      (node (ref "U21") (pin "17") (pinfunction "EP_17") (pintype "passive"))
      (node (ref "U21") (pin "6") (pinfunction "GND_6") (pintype "passive"))
      (node (ref "Y1") (pin "2") (pinfunction "NC_1_2") (pintype "passive"))
      (node (ref "Y1") (pin "4") (pinfunction "NC_2_4") (pintype "passive"))
    )
    (net (code "30") (name "Net-(BR1-+)") (class "Default")
      (node (ref "BR1") (pin "1") (pinfunction "+_1") (pintype "passive"))
      (node (ref "BR2") (pin "1") (pinfunction "+_1") (pintype "passive"))
      (node (ref "D1") (pin "2") (pinfunction "A_2") (pintype "passive"))
      (node (ref "Q1") (pin "2") (pinfunction "S_2") (pintype "passive"))
      (node (ref "R1") (pin "1") (pinfunction "1_1") (pintype "passive"))
      (node (ref "VPE") (pin "1") (pinfunction "TP_1") (pintype "passive"))
    )
    (net (code "31") (name "Net-(C11-Pad1)") (class "Default")
      (node (ref "C11") (pin "1") (pinfunction "1_1") (pintype "passive"))
      (node (ref "R23") (pin "1") (pinfunction "1_1") (pintype "passive"))
    )
    (net (code "32") (name "Net-(C16-Pad1)") (class "Default")
      (node (ref "C16") (pin "1") (pinfunction "1_1") (pintype "passive"))
      (node (ref "R20") (pin "2") (pinfunction "2_2") (pintype "passive"))
      (node (ref "R21") (pin "2") (pinfunction "2_2") (pintype "passive"))
    )
    (net (code "33") (name "Net-(C17-Pad1)") (class "Default")
      (node (ref "C17") (pin "1") (pinfunction "1_1") (pintype "passive"))
      (node (ref "R22") (pin "2") (pinfunction "2_2") (pintype "passive"))
      (node (ref "R23") (pin "2") (pinfunction "2_2") (pintype "passive"))
    )
    (net (code "34") (name "Net-(C21-Pad1)") (class "Default")
      (node (ref "C21") (pin "1") (pinfunction "1_1") (pintype "passive"))
      (node (ref "R20") (pin "1") (pinfunction "1_1") (pintype "passive"))
    )
    (net (code "35") (name "Net-(C22-Pad1)") (class "Default")
      (node (ref "C22") (pin "1") (pinfunction "1_1") (pintype "passive"))
      (node (ref "R21") (pin "1") (pinfunction "1_1") (pintype "passive"))
    )
    (net (code "36") (name "Net-(C23-Pad1)") (class "Default")
      (node (ref "C23") (pin "1") (pinfunction "1_1") (pintype "passive"))
      (node (ref "R22") (pin "1") (pinfunction "1_1") (pintype "passive"))
    )
    (net (code "37") (name "Net-(D1-K)") (class "Default")
      (node (ref "D1") (pin "1") (pinfunction "K_1") (pintype "passive"))
      (node (ref "Q1") (pin "1") (pinfunction "G_1") (pintype "passive"))
      (node (ref "R1") (pin "2") (pinfunction "2_2") (pintype "passive"))
      (node (ref "R2") (pin "1") (pinfunction "1_1") (pintype "passive"))
    )
    (net (code "38") (name "Net-(D2-A)") (class "Default")
      (node (ref "D2") (pin "2") (pinfunction "A_2") (pintype "passive"))
      (node (ref "J4") (pin "2") (pinfunction "2_2") (pintype "passive"))
      (node (ref "J5") (pin "2") (pinfunction "2_2") (pintype "passive"))
      (node (ref "Q2") (pin "2") (pinfunction "S_2") (pintype "passive"))
      (node (ref "R3") (pin "1") (pinfunction "1_1") (pintype "passive"))
      (node (ref "WADE") (pin "1") (pinfunction "TP_1") (pintype "passive"))
    )
    (net (code "39") (name "Net-(D2-K)") (class "Default")
      (node (ref "D2") (pin "1") (pinfunction "K_1") (pintype "passive"))
      (node (ref "Q2") (pin "1") (pinfunction "G_1") (pintype "passive"))
      (node (ref "R3") (pin "2") (pinfunction "2_2") (pintype "passive"))
      (node (ref "R4") (pin "1") (pinfunction "1_1") (pintype "passive"))
    )
    (net (code "40") (name "Net-(D6-K)") (class "Default")
      (node (ref "D6") (pin "1") (pinfunction "K_1") (pintype "passive"))
      (node (ref "Q6") (pin "1") (pinfunction "G_1") (pintype "passive"))
      (node (ref "R6") (pin "1") (pinfunction "1_1") (pintype "passive"))
    )
    (net (code "41") (name "Net-(D8-K)") (class "Default")
      (node (ref "C34") (pin "1") (pinfunction "1_1") (pintype "passive"))
      (node (ref "D8") (pin "1") (pinfunction "K_1") (pintype "passive"))
      (node (ref "Q1") (pin "3") (pinfunction "D_3") (pintype "passive"))
      (node (ref "U21") (pin "13") (pinfunction "VDD_13") (pintype "passive"))
      (node (ref "VP") (pin "1") (pinfunction "TP_1") (pintype "passive"))
    )
    (net (code "42") (name "Net-(D9-K)") (class "Default")
      (node (ref "C35") (pin "1") (pinfunction "1_1") (pintype "passive"))
      (node (ref "C36") (pin "1") (pinfunction "1_1") (pintype "passive"))
      (node (ref "D9") (pin "1") (pinfunction "K_1") (pintype "passive"))
      (node (ref "U21") (pin "14") (pinfunction "VCC_14") (pintype "passive"))
      (node (ref "VWADD") (pin "1") (pinfunction "TP_1") (pintype "passive"))
    )
    (net (code "43") (name "Net-(Q2-D)") (class "Default")
      (node (ref "Q2") (pin "3") (pinfunction "D_3") (pintype "passive"))
      (node (ref "Q6") (pin "3") (pinfunction "D_3") (pintype "passive"))
    )
    (net (code "44") (name "Net-(S1-1_C)") (class "Default")
      (node (ref "R4") (pin "2") (pinfunction "2_2") (pintype "passive"))
      (node (ref "S1") (pin "2") (pinfunction "1_C_2") (pintype "passive"))
    )
    (net (code "45") (name "Net-(TR1-RDCT)") (class "Default")
      (node (ref "C19") (pin "1") (pinfunction "1_1") (pintype "passive"))
      (node (ref "R40") (pin "1") (pinfunction "1_1") (pintype "passive"))
      (node (ref "TR1") (pin "7") (pinfunction "RDCT_7") (pintype "passive"))
    )
    (net (code "46") (name "Net-(TR1-TD+)") (class "Default")
      (node (ref "C7") (pin "1") (pinfunction "1_1") (pintype "passive"))
      (node (ref "TR1") (pin "1") (pinfunction "TD+_1") (pintype "passive"))
    )
    (net (code "47") (name "Net-(TR1-TD-)") (class "Default")
      (node (ref "C10") (pin "1") (pinfunction "1_1") (pintype "passive"))
      (node (ref "TR1") (pin "3") (pinfunction "TD-_3") (pintype "passive"))
    )
    (net (code "48") (name "Net-(TR1-TDCT)") (class "Default")
      (node (ref "C26") (pin "1") (pinfunction "1_1") (pintype "passive"))
      (node (ref "R26") (pin "1") (pinfunction "1_1") (pintype "passive"))
      (node (ref "R27") (pin "1") (pinfunction "1_1") (pintype "passive"))
      (node (ref "TR1") (pin "2") (pinfunction "TDCT_2") (pintype "passive"))
    )
    (net (code "49") (name "Net-(U20-1V2O)") (class "Default")
      (node (ref "C5") (pin "1") (pinfunction "1_1") (pintype "passive"))
      (node (ref "U20") (pin "22") (pinfunction "1V2O_22") (pintype "passive"))
    )
    (net (code "50") (name "Net-(U20-EXRES1)") (class "Default")
      (node (ref "C6") (pin "1") (pinfunction "1_1") (pintype "passive"))
      (node (ref "R31") (pin "1") (pinfunction "1_1") (pintype "passive"))
      (node (ref "U20") (pin "10") (pinfunction "EXRES1_10") (pintype "passive"))
      (node (ref "U20") (pin "20") (pinfunction "TOCAP_20") (pintype "passive"))
    )
    (net (code "51") (name "Net-(U20-PMODE0)") (class "Default")
      (node (ref "R39") (pin "2") (pinfunction "2_2") (pintype "passive"))
      (node (ref "U20") (pin "45") (pinfunction "PMODE0_45") (pintype "passive"))
    )
    (net (code "52") (name "Net-(U20-PMODE1)") (class "Default")
      (node (ref "R38") (pin "2") (pinfunction "2_2") (pintype "passive"))
      (node (ref "U20") (pin "44") (pinfunction "PMODE1_44") (pintype "passive"))
    )
    (net (code "53") (name "Net-(U20-PMODE2)") (class "Default")
      (node (ref "R37") (pin "2") (pinfunction "2_2") (pintype "passive"))
      (node (ref "U20") (pin "43") (pinfunction "PMODE2_43") (pintype "passive"))
    )
    (net (code "54") (name "Net-(U20-VDD)") (class "Default")
      (node (ref "C33") (pin "1") (pinfunction "1_1") (pintype "passive"))
      (node (ref "C9") (pin "1") (pinfunction "1_1") (pintype "passive"))
      (node (ref "U20") (pin "28") (pinfunction "VDD_28") (pintype "passive"))
    )
    (net (code "55") (name "Net-(U21-CLASS2)") (class "Default")
      (node (ref "C37") (pin "2") (pinfunction "2_2") (pintype "passive"))
      (node (ref "U21") (pin "10") (pinfunction "CLASS2_10") (pintype "passive"))
      (node (ref "U21") (pin "7") (pinfunction "VDRV_7") (pintype "passive"))
    )
    (net (code "56") (name "Net-(U21-FB)") (class "Default")
      (node (ref "R32") (pin "2") (pinfunction "2_2") (pintype "passive"))
      (node (ref "R33") (pin "2") (pinfunction "2_2") (pintype "passive"))
      (node (ref "U21") (pin "5") (pinfunction "FB_5") (pintype "passive"))
    )
    (net (code "57") (name "Net-(U21-LX)") (class "Default")
      (node (ref "L4") (pin "1") (pinfunction "1_1") (pintype "passive"))
      (node (ref "U21") (pin "2") (pinfunction "LX_2") (pintype "passive"))
    )
    (net (code "58") (name "Net-(U21-RREF)") (class "Default")
      (node (ref "R34") (pin "1") (pinfunction "1_1") (pintype "passive"))
      (node (ref "U21") (pin "16") (pinfunction "RREF_16") (pintype "passive"))
    )
    (net (code "59") (name "Net-(U21-~{SL})") (class "Default")
      (node (ref "R35") (pin "1") (pinfunction "1_1") (pintype "passive"))
      (node (ref "U21") (pin "8") (pinfunction "~{SL}_8") (pintype "passive"))
    )
    (net (code "60") (name "PGND") (class "Default")
      (node (ref "BR1") (pin "3") (pinfunction "-_3") (pintype "passive"))
      (node (ref "BR2") (pin "3") (pinfunction "-_3") (pintype "passive"))
      (node (ref "C12") (pin "2") (pinfunction "2_2") (pintype "passive"))
      (node (ref "C34") (pin "2") (pinfunction "2_2") (pintype "passive"))
      (node (ref "C35") (pin "2") (pinfunction "2_2") (pintype "passive"))
      (node (ref "C36") (pin "2") (pinfunction "2_2") (pintype "passive"))
      (node (ref "C38") (pin "1") (pinfunction "1_1") (pintype "passive"))
      (node (ref "C39") (pin "2") (pinfunction "2_2") (pintype "passive"))
      (node (ref "J4") (pin "1") (pinfunction "1_1") (pintype "passive"))
      (node (ref "J5") (pin "1") (pinfunction "1_1") (pintype "passive"))
      (node (ref "PGND") (pin "1") (pinfunction "TP_1") (pintype "passive"))
      (node (ref "R36") (pin "1") (pinfunction "1_1") (pintype "passive"))
      (node (ref "R6") (pin "2") (pinfunction "2_2") (pintype "passive"))
      (node (ref "S1") (pin "1") (pinfunction "1_1") (pintype "passive"))
      (node (ref "S1") (pin "5") (pinfunction "5_5") (pintype "passive"))
      (node (ref "U21") (pin "15") (pinfunction "PGND_15") (pintype "passive"))
    )
    (net (code "61") (name "unconnected-(S1-Pad3)") (class "Default")
      (node (ref "S1") (pin "3") (pinfunction "3_3") (pintype "passive+no_connect"))
    )
    (net (code "62") (name "unconnected-(S1-Pad7)") (class "Default")
      (node (ref "S1") (pin "7") (pinfunction "7_7") (pintype "passive+no_connect"))
    )
    (net (code "63") (name "unconnected-(U20-DNC-Pad7)") (class "Default")
      (node (ref "U20") (pin "7") (pinfunction "DNC_7") (pintype "passive+no_connect"))
    )
    (net (code "64") (name "unconnected-(U20-DUPLED-Pad26)") (class "Default")
      (node (ref "U20") (pin "26") (pinfunction "DUPLED_26") (pintype "passive+no_connect"))
    )
    (net (code "65") (name "unconnected-(U20-NC_1-Pad12)") (class "Default")
      (node (ref "U20") (pin "12") (pinfunction "NC_1_12") (pintype "passive+no_connect"))
    )
    (net (code "66") (name "unconnected-(U20-NC_2-Pad13)") (class "Default")
      (node (ref "U20") (pin "13") (pinfunction "NC_2_13") (pintype "passive+no_connect"))
    )
    (net (code "67") (name "unconnected-(U20-NC_3-Pad46)") (class "Default")
      (node (ref "U20") (pin "46") (pinfunction "NC_3_46") (pintype "passive+no_connect"))
    )
    (net (code "68") (name "unconnected-(U20-NC_4-Pad47)") (class "Default")
      (node (ref "U20") (pin "47") (pinfunction "NC_4_47") (pintype "passive+no_connect"))
    )
    (net (code "69") (name "unconnected-(U20-RSVD_1-Pad23)") (class "Default")
      (node (ref "U20") (pin "23") (pinfunction "RSVD_1_23") (pintype "passive+no_connect"))
    )
    (net (code "70") (name "unconnected-(U20-RSVD_2-Pad38)") (class "Default")
      (node (ref "U20") (pin "38") (pinfunction "RSVD_2_38") (pintype "passive+no_connect"))
    )
    (net (code "71") (name "unconnected-(U20-RSVD_3-Pad39)") (class "Default")
      (node (ref "U20") (pin "39") (pinfunction "RSVD_3_39") (pintype "passive+no_connect"))
    )
    (net (code "72") (name "unconnected-(U20-RSVD_4-Pad40)") (class "Default")
      (node (ref "U20") (pin "40") (pinfunction "RSVD_4_40") (pintype "passive+no_connect"))
    )
    (net (code "73") (name "unconnected-(U20-RSVD_5-Pad41)") (class "Default")
      (node (ref "U20") (pin "41") (pinfunction "RSVD_5_41") (pintype "passive+no_connect"))
    )
    (net (code "74") (name "unconnected-(U20-RSVD_6-Pad42)") (class "Default")
      (node (ref "U20") (pin "42") (pinfunction "RSVD_6_42") (pintype "passive+no_connect"))
    )
    (net (code "75") (name "unconnected-(U20-SPDLED-Pad24)") (class "Default")
      (node (ref "U20") (pin "24") (pinfunction "SPDLED_24") (pintype "passive+no_connect"))
    )
    (net (code "76") (name "unconnected-(U20-VBG-Pad18)") (class "Default")
      (node (ref "U20") (pin "18") (pinfunction "VBG_18") (pintype "passive+no_connect"))
    )
    (net (code "77") (name "unconnected-(U21-LED-Pad3)") (class "Default")
      (node (ref "U21") (pin "3") (pinfunction "LED_3") (pintype "passive+no_connect"))
    )
    (net (code "78") (name "unconnected-(U21-MPS-Pad11)") (class "Default")
      (node (ref "U21") (pin "11") (pinfunction "MPS_11") (pintype "passive+no_connect"))
    )
    (net (code "79") (name "unconnected-(U21-~{ULP}-Pad9)") (class "Default")
      (node (ref "U21") (pin "9") (pinfunction "~{ULP}_9") (pintype "passive+no_connect"))
    )
    (net (code "80") (name "unconnected-(U21-~{WK}-Pad4)") (class "Default")
      (node (ref "U21") (pin "4") (pinfunction "~{WK}_4") (pintype "passive+no_connect"))
    )
  )
)
